# stripPCB002.net
KiCad netlist of a schematic drawn in EAGLE
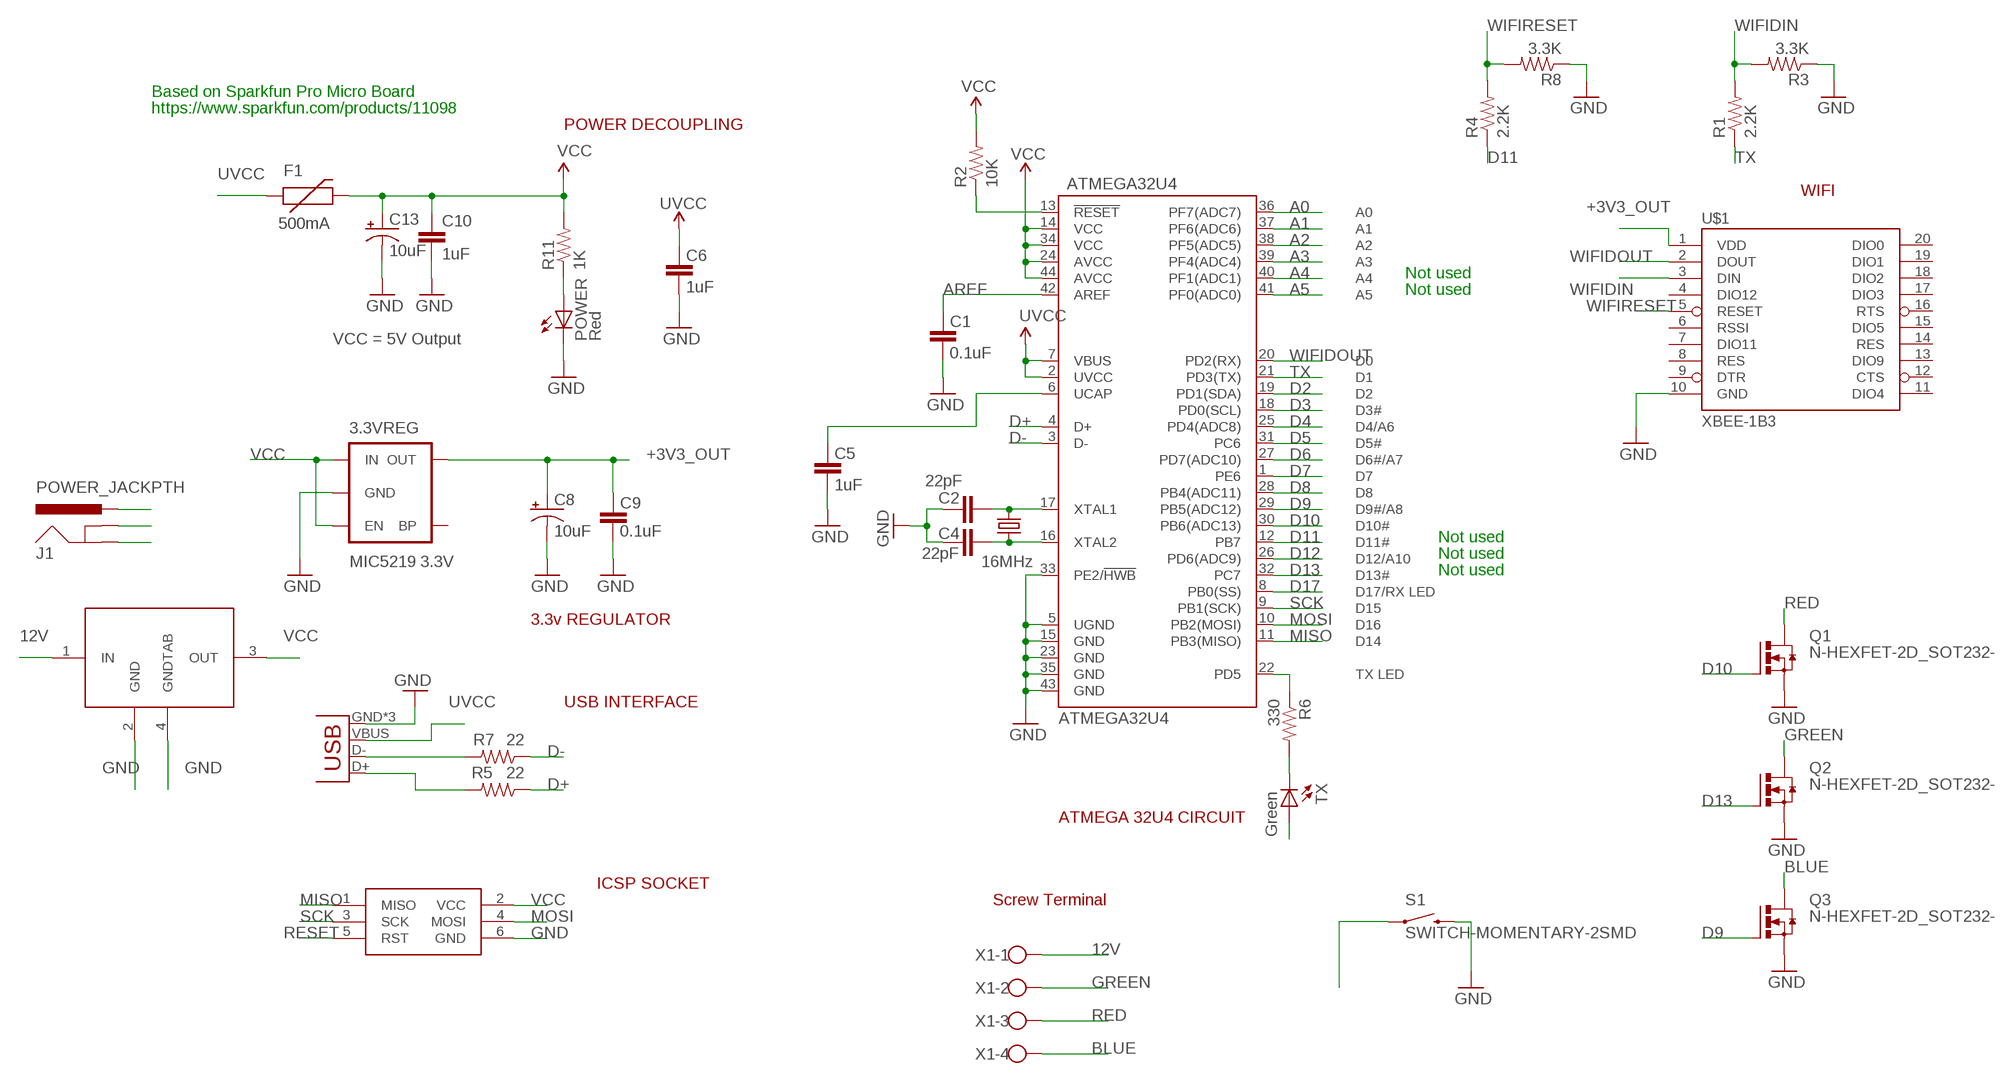
[diagram p0: schematic, sheet 1]

(export (version "E")
  (design (tool "Eeschema 10.0.6"))
  (components
    (comp (ref "3.3VREG")
      (value "MIC5219 3.3V")
      (footprint "eagle-import:SOT23-5")
      (libsource (lib "eagle-import") (part "V_REG_MIC52193.3V"))
    )
    (comp (ref "ATMEGA32U4")
      (value "ATMEGA32U4")
      (footprint "eagle-import:SPARKFUN-DIGITALIC_TQFP44")
      (libsource (lib "eagle-import") (part "ATMEGA32U4TQFP"))
    )
    (comp (ref "C1")
      (value "0.1uF")
      (footprint "eagle-import:0402-CAP")
      (libsource (lib "eagle-import") (part "CAP0402-CAP"))
    )
    (comp (ref "C2")
      (value "22pF")
      (footprint "eagle-import:0402-CAP")
      (libsource (lib "eagle-import") (part "CAP0402-CAP"))
    )
    (comp (ref "C4")
      (value "22pF")
      (footprint "eagle-import:0402-CAP")
      (libsource (lib "eagle-import") (part "CAP0402-CAP"))
    )
    (comp (ref "C5")
      (value "1uF")
      (footprint "eagle-import:0402-CAP")
      (libsource (lib "eagle-import") (part "CAP0402-CAP"))
    )
    (comp (ref "C6")
      (value "1uF")
      (footprint "eagle-import:0402-CAP")
      (libsource (lib "eagle-import") (part "CAP0402-CAP"))
    )
    (comp (ref "C8")
      (value "10uF")
      (footprint "eagle-import:EIA3216")
      (libsource (lib "eagle-import") (part "CAP_POL1206"))
    )
    (comp (ref "C9")
      (value "0.1uF")
      (footprint "eagle-import:0402-CAP")
      (libsource (lib "eagle-import") (part "CAP0402-CAP"))
    )
    (comp (ref "C10")
      (value "1uF")
      (footprint "eagle-import:0402-CAP")
      (libsource (lib "eagle-import") (part "CAP0402-CAP"))
    )
    (comp (ref "C13")
      (value "10uF")
      (footprint "eagle-import:EIA3216")
      (libsource (lib "eagle-import") (part "CAP_POL1206"))
    )
    (comp (ref "F1")
      (value "500mA")
      (footprint "eagle-import:PTC-1206")
      (libsource (lib "eagle-import") (part "PTCSMD"))
    )
    (comp (ref "ISP1")
      (value "AVRISP-6")
      (footprint "eagle-import:AVRISP")
      (libsource (lib "eagle-import") (part "AVRISP-6"))
    )
    (comp (ref "J1")
      (value "POWER_JACKPTH")
      (footprint "eagle-import:POWER_JACK_PTH")
      (libsource (lib "eagle-import") (part "POWER_JACKPTH"))
    )
    (comp (ref "POWER")
      (value "Red")
      (footprint "eagle-import:LED-0603")
      (libsource (lib "eagle-import") (part "LED0603"))
    )
    (comp (ref "Q1")
      (value "N-HEXFET-2D_SOT232-")
      (footprint "eagle-import:SOT223")
      (libsource (lib "eagle-import") (part "N-HEXFET-2D_?-SOT232"))
    )
    (comp (ref "Q2")
      (value "N-HEXFET-2D_SOT232-")
      (footprint "eagle-import:SOT223")
      (libsource (lib "eagle-import") (part "N-HEXFET-2D_?-SOT232"))
    )
    (comp (ref "Q3")
      (value "N-HEXFET-2D_SOT232-")
      (footprint "eagle-import:SOT223")
      (libsource (lib "eagle-import") (part "N-HEXFET-2D_?-SOT232"))
    )
    (comp (ref "R1")
      (value "2.2K")
      (footprint "eagle-import:0402-RES")
      (libsource (lib "eagle-import") (part "RESISTOR0402-RES"))
    )
    (comp (ref "R2")
      (value "10K")
      (footprint "eagle-import:0402-RES")
      (libsource (lib "eagle-import") (part "RESISTOR0402-RES"))
    )
    (comp (ref "R3")
      (value "3.3K")
      (footprint "eagle-import:0402-RES")
      (libsource (lib "eagle-import") (part "RESISTOR0402-RES"))
    )
    (comp (ref "R4")
      (value "2.2K")
      (footprint "eagle-import:0402-RES")
      (libsource (lib "eagle-import") (part "RESISTOR0402-RES"))
    )
    (comp (ref "R5")
      (value "22")
      (footprint "eagle-import:0402-RES")
      (libsource (lib "eagle-import") (part "RESISTOR0402-RES"))
    )
    (comp (ref "R6")
      (value "330")
      (footprint "eagle-import:0402-RES")
      (libsource (lib "eagle-import") (part "RESISTOR0402-RES"))
    )
    (comp (ref "R7")
      (value "22")
      (footprint "eagle-import:0402-RES")
      (libsource (lib "eagle-import") (part "RESISTOR0402-RES"))
    )
    (comp (ref "R8")
      (value "3.3K")
      (footprint "eagle-import:0402-RES")
      (libsource (lib "eagle-import") (part "RESISTOR0402-RES"))
    )
    (comp (ref "R11")
      (value "1K")
      (footprint "eagle-import:0402-RES")
      (libsource (lib "eagle-import") (part "RESISTOR0402-RES"))
    )
    (comp (ref "S1")
      (value "SWITCH-MOMENTARY-2SMD")
      (footprint "eagle-import:TACTILE_SWITCH_SMD")
      (libsource (lib "eagle-import") (part "SWITCH-MOMENTARY-2SMD"))
    )
    (comp (ref "TX")
      (value "Green")
      (footprint "eagle-import:LED-0603")
      (libsource (lib "eagle-import") (part "LED0603"))
    )
    (comp (ref "U$1")
      (value "XBEE-1B3")
      (footprint "eagle-import:XBEE-SMD")
      (libsource (lib "eagle-import") (part "XBEE-1B3"))
    )
    (comp (ref "U$2")
      (value "MIC5239")
      (footprint "eagle-import:SOT223")
      (libsource (lib "eagle-import") (part "MIC5239"))
    )
    (comp (ref "X1")
      (value "W237-4")
      (footprint "eagle-import:W237-4")
      (libsource (lib "eagle-import") (part "W237-4"))
    )
    (comp (ref "X2")
      (value "USB-MICROB")
      (footprint "eagle-import:USB-MICROB")
      (libsource (lib "eagle-import") (part "USB-MICROB"))
    )
    (comp (ref "Y1")
      (value "16MHz")
      (footprint "eagle-import:CRYSTAL-SMD-5X3")
      (libsource (lib "eagle-import") (part "CRYSTAL5X3"))
    )
  )
  (nets
    (net (code "1") (name "/+3V3_OUT") (class "Default")
      (node (ref "3.3VREG") (pin "5") (pinfunction "OUT_5") (pintype "passive"))
      (node (ref "C8") (pin "A") (pinfunction "+_A") (pintype "passive"))
      (node (ref "C9") (pin "2") (pinfunction "2_2") (pintype "passive"))
      (node (ref "U$1") (pin "1") (pinfunction "VDD_1") (pintype "power_in"))
    )
    (net (code "2") (name "/12V") (class "Default")
      (node (ref "J1") (pin "PWR") (pinfunction "PWR_PWR") (pintype "bidirectional"))
      (node (ref "U$2") (pin "1") (pinfunction "IN_1") (pintype "input"))
      (node (ref "X1") (pin "1") (pinfunction "KL_1") (pintype "passive"))
    )
    (net (code "3") (name "/A0") (class "Default")
      (node (ref "ATMEGA32U4") (pin "36") (pinfunction "PF7(ADC7)_36") (pintype "bidirectional"))
    )
    (net (code "4") (name "/A1") (class "Default")
      (node (ref "ATMEGA32U4") (pin "37") (pinfunction "PF6(ADC6)_37") (pintype "bidirectional"))
    )
    (net (code "5") (name "/A2") (class "Default")
      (node (ref "ATMEGA32U4") (pin "38") (pinfunction "PF5(ADC5)_38") (pintype "bidirectional"))
    )
    (net (code "6") (name "/A3") (class "Default")
      (node (ref "ATMEGA32U4") (pin "39") (pinfunction "PF4(ADC4)_39") (pintype "bidirectional"))
    )
    (net (code "7") (name "/A4") (class "Default")
      (node (ref "ATMEGA32U4") (pin "40") (pinfunction "PF1(ADC1)_40") (pintype "bidirectional"))
    )
    (net (code "8") (name "/A5") (class "Default")
      (node (ref "ATMEGA32U4") (pin "41") (pinfunction "PF0(ADC0)_41") (pintype "bidirectional"))
    )
    (net (code "9") (name "/AREF") (class "Default")
      (node (ref "ATMEGA32U4") (pin "42") (pinfunction "AREF_42") (pintype "bidirectional"))
      (node (ref "C1") (pin "2") (pinfunction "2_2") (pintype "passive"))
    )
    (net (code "10") (name "/BLUE") (class "Default")
      (node (ref "Q3") (pin "2") (pinfunction "D_2") (pintype "passive"))
      (node (ref "Q3") (pin "4") (pinfunction "D_4") (pintype "passive"))
      (node (ref "X1") (pin "4") (pinfunction "KL_4") (pintype "passive"))
    )
    (net (code "11") (name "/D+") (class "Default")
      (node (ref "ATMEGA32U4") (pin "4") (pinfunction "D+_4") (pintype "bidirectional"))
      (node (ref "R5") (pin "1") (pinfunction "1_1") (pintype "passive"))
    )
    (net (code "12") (name "/D-") (class "Default")
      (node (ref "ATMEGA32U4") (pin "3") (pinfunction "D-_3") (pintype "bidirectional"))
      (node (ref "R7") (pin "1") (pinfunction "1_1") (pintype "passive"))
    )
    (net (code "13") (name "/D2") (class "Default")
      (node (ref "ATMEGA32U4") (pin "19") (pinfunction "PD1(SDA)_19") (pintype "bidirectional"))
    )
    (net (code "14") (name "/D3") (class "Default")
      (node (ref "ATMEGA32U4") (pin "18") (pinfunction "PD0(SCL)_18") (pintype "bidirectional"))
    )
    (net (code "15") (name "/D4") (class "Default")
      (node (ref "ATMEGA32U4") (pin "25") (pinfunction "PD4(ADC8)_25") (pintype "bidirectional"))
    )
    (net (code "16") (name "/D5") (class "Default")
      (node (ref "ATMEGA32U4") (pin "31") (pinfunction "PC6_31") (pintype "bidirectional"))
    )
    (net (code "17") (name "/D6") (class "Default")
      (node (ref "ATMEGA32U4") (pin "27") (pinfunction "PD7(ADC10)_27") (pintype "bidirectional"))
    )
    (net (code "18") (name "/D7") (class "Default")
      (node (ref "ATMEGA32U4") (pin "1") (pinfunction "PE6_1") (pintype "bidirectional"))
      (node (ref "S1") (pin "1") (pinfunction "1_1") (pintype "passive"))
    )
    (net (code "19") (name "/D8") (class "Default")
      (node (ref "ATMEGA32U4") (pin "28") (pinfunction "PB4(ADC11)_28") (pintype "bidirectional"))
    )
    (net (code "20") (name "/D9") (class "Default")
      (node (ref "ATMEGA32U4") (pin "29") (pinfunction "PB5(ADC12)_29") (pintype "bidirectional"))
      (node (ref "Q3") (pin "1") (pinfunction "G_1") (pintype "passive"))
    )
    (net (code "21") (name "/D10") (class "Default")
      (node (ref "ATMEGA32U4") (pin "30") (pinfunction "PB6(ADC13)_30") (pintype "bidirectional"))
      (node (ref "Q1") (pin "1") (pinfunction "G_1") (pintype "passive"))
    )
    (net (code "22") (name "/D11") (class "Default")
      (node (ref "ATMEGA32U4") (pin "12") (pinfunction "PB7_12") (pintype "bidirectional"))
      (node (ref "R4") (pin "1") (pinfunction "1_1") (pintype "passive"))
    )
    (net (code "23") (name "/D12") (class "Default")
      (node (ref "ATMEGA32U4") (pin "26") (pinfunction "PD6(ADC9)_26") (pintype "bidirectional"))
    )
    (net (code "24") (name "/D13") (class "Default")
      (node (ref "ATMEGA32U4") (pin "32") (pinfunction "PC7_32") (pintype "bidirectional"))
      (node (ref "Q2") (pin "1") (pinfunction "G_1") (pintype "passive"))
    )
    (net (code "25") (name "/D17") (class "Default")
      (node (ref "ATMEGA32U4") (pin "8") (pinfunction "PB0(SS)_8") (pintype "bidirectional"))
    )
    (net (code "26") (name "/GREEN") (class "Default")
      (node (ref "Q2") (pin "2") (pinfunction "D_2") (pintype "passive"))
      (node (ref "Q2") (pin "4") (pinfunction "D_4") (pintype "passive"))
      (node (ref "X1") (pin "2") (pinfunction "KL_2") (pintype "passive"))
    )
    (net (code "27") (name "/MISO") (class "Default")
      (node (ref "ATMEGA32U4") (pin "11") (pinfunction "PB3(MISO)_11") (pintype "bidirectional"))
      (node (ref "ISP1") (pin "1") (pinfunction "MISO_1") (pintype "input"))
    )
    (net (code "28") (name "/MOSI") (class "Default")
      (node (ref "ATMEGA32U4") (pin "10") (pinfunction "PB2(MOSI)_10") (pintype "bidirectional"))
      (node (ref "ISP1") (pin "4") (pinfunction "MOSI_4") (pintype "output"))
    )
    (net (code "29") (name "/RED") (class "Default")
      (node (ref "Q1") (pin "2") (pinfunction "D_2") (pintype "passive"))
      (node (ref "Q1") (pin "4") (pinfunction "D_4") (pintype "passive"))
      (node (ref "X1") (pin "3") (pinfunction "KL_3") (pintype "passive"))
    )
    (net (code "30") (name "/RESET") (class "Default")
      (node (ref "ATMEGA32U4") (pin "13") (pinfunction "~{RESET}_13") (pintype "bidirectional"))
      (node (ref "ISP1") (pin "5") (pinfunction "RST_5") (pintype "output"))
      (node (ref "R2") (pin "1") (pinfunction "1_1") (pintype "passive"))
    )
    (net (code "31") (name "/SCK") (class "Default")
      (node (ref "ATMEGA32U4") (pin "9") (pinfunction "PB1(SCK)_9") (pintype "bidirectional"))
      (node (ref "ISP1") (pin "3") (pinfunction "SCK_3") (pintype "output"))
    )
    (net (code "32") (name "/TX") (class "Default")
      (node (ref "ATMEGA32U4") (pin "21") (pinfunction "PD3(TX)_21") (pintype "bidirectional"))
      (node (ref "R1") (pin "1") (pinfunction "1_1") (pintype "passive"))
    )
    (net (code "33") (name "/WIFIDIN") (class "Default")
      (node (ref "R1") (pin "2") (pinfunction "2_2") (pintype "passive"))
      (node (ref "R3") (pin "2") (pinfunction "2_2") (pintype "passive"))
      (node (ref "U$1") (pin "3") (pinfunction "DIN_3") (pintype "input"))
    )
    (net (code "34") (name "/WIFIDOUT") (class "Default")
      (node (ref "ATMEGA32U4") (pin "20") (pinfunction "PD2(RX)_20") (pintype "bidirectional"))
      (node (ref "U$1") (pin "2") (pinfunction "DOUT_2") (pintype "output"))
    )
    (net (code "35") (name "/WIFIRESET") (class "Default")
      (node (ref "R4") (pin "2") (pinfunction "2_2") (pintype "passive"))
      (node (ref "R8") (pin "2") (pinfunction "2_2") (pintype "passive"))
      (node (ref "U$1") (pin "5") (pinfunction "RESET_5") (pintype "input"))
    )
    (net (code "36") (name "GND") (class "Default")
      (node (ref "3.3VREG") (pin "2") (pinfunction "GND_2") (pintype "input"))
      (node (ref "ATMEGA32U4") (pin "15") (pinfunction "GND_15") (pintype "bidirectional"))
      (node (ref "ATMEGA32U4") (pin "23") (pinfunction "GND_23") (pintype "bidirectional"))
      (node (ref "ATMEGA32U4") (pin "33") (pinfunction "PE2/~{HWB}_33") (pintype "bidirectional"))
      (node (ref "ATMEGA32U4") (pin "35") (pinfunction "GND_35") (pintype "bidirectional"))
      (node (ref "ATMEGA32U4") (pin "43") (pinfunction "GND_43") (pintype "bidirectional"))
      (node (ref "ATMEGA32U4") (pin "5") (pinfunction "UGND_5") (pintype "bidirectional"))
      (node (ref "C1") (pin "1") (pinfunction "1_1") (pintype "passive"))
      (node (ref "C10") (pin "2") (pinfunction "2_2") (pintype "passive"))
      (node (ref "C13") (pin "C") (pinfunction "-_C") (pintype "passive"))
      (node (ref "C2") (pin "2") (pinfunction "2_2") (pintype "passive"))
      (node (ref "C4") (pin "2") (pinfunction "2_2") (pintype "passive"))
      (node (ref "C5") (pin "1") (pinfunction "1_1") (pintype "passive"))
      (node (ref "C6") (pin "1") (pinfunction "1_1") (pintype "passive"))
      (node (ref "C8") (pin "C") (pinfunction "-_C") (pintype "passive"))
      (node (ref "C9") (pin "1") (pinfunction "1_1") (pintype "passive"))
      (node (ref "ISP1") (pin "6") (pinfunction "GND_6") (pintype "power_in"))
      (node (ref "J1") (pin "GND") (pinfunction "GND_GND") (pintype "bidirectional"))
      (node (ref "J1") (pin "GNDBREAK") (pinfunction "GNDBREAK_GNDBREAK") (pintype "bidirectional"))
      (node (ref "POWER") (pin "C") (pinfunction "C_C") (pintype "passive"))
      (node (ref "Q1") (pin "3") (pinfunction "S_3") (pintype "passive"))
      (node (ref "Q2") (pin "3") (pinfunction "S_3") (pintype "passive"))
      (node (ref "Q3") (pin "3") (pinfunction "S_3") (pintype "passive"))
      (node (ref "R3") (pin "1") (pinfunction "1_1") (pintype "passive"))
      (node (ref "R8") (pin "1") (pinfunction "1_1") (pintype "passive"))
      (node (ref "S1") (pin "3") (pinfunction "2_3") (pintype "passive"))
      (node (ref "U$1") (pin "10") (pinfunction "GND_10") (pintype "power_in"))
      (node (ref "U$2") (pin "2") (pinfunction "GND_2") (pintype "power_in"))
      (node (ref "U$2") (pin "4") (pinfunction "GNDTAB_4") (pintype "power_in"))
      (node (ref "X2") (pin "GND") (pinfunction "GND_GND") (pintype "bidirectional"))
      (node (ref "X2") (pin "MT1") (pinfunction "GND_MT1") (pintype "bidirectional"))
      (node (ref "X2") (pin "MT2") (pinfunction "GND_MT2") (pintype "bidirectional"))
    )
    (net (code "37") (name "Net-(ATMEGA32U4-PD5)") (class "Default")
      (node (ref "ATMEGA32U4") (pin "22") (pinfunction "PD5_22") (pintype "bidirectional"))
      (node (ref "R6") (pin "1") (pinfunction "1_1") (pintype "passive"))
    )
    (net (code "38") (name "Net-(ATMEGA32U4-UCAP)") (class "Default")
      (node (ref "ATMEGA32U4") (pin "6") (pinfunction "UCAP_6") (pintype "bidirectional"))
      (node (ref "C5") (pin "2") (pinfunction "2_2") (pintype "passive"))
    )
    (net (code "39") (name "Net-(ATMEGA32U4-XTAL1)") (class "Default")
      (node (ref "ATMEGA32U4") (pin "17") (pinfunction "XTAL1_17") (pintype "bidirectional"))
      (node (ref "C2") (pin "1") (pinfunction "1_1") (pintype "passive"))
      (node (ref "Y1") (pin "3") (pinfunction "2_3") (pintype "passive"))
    )
    (net (code "40") (name "Net-(ATMEGA32U4-XTAL2)") (class "Default")
      (node (ref "ATMEGA32U4") (pin "16") (pinfunction "XTAL2_16") (pintype "bidirectional"))
      (node (ref "C4") (pin "1") (pinfunction "1_1") (pintype "passive"))
      (node (ref "Y1") (pin "1") (pinfunction "1_1") (pintype "passive"))
    )
    (net (code "41") (name "Net-(POWER-PadA)") (class "Default")
      (node (ref "POWER") (pin "A") (pinfunction "A_A") (pintype "passive"))
      (node (ref "R11") (pin "1") (pinfunction "1_1") (pintype "passive"))
    )
    (net (code "42") (name "Net-(R5-Pad2)") (class "Default")
      (node (ref "R5") (pin "2") (pinfunction "2_2") (pintype "passive"))
      (node (ref "X2") (pin "D+") (pinfunction "D+_D+") (pintype "bidirectional"))
    )
    (net (code "43") (name "Net-(R6-Pad2)") (class "Default")
      (node (ref "R6") (pin "2") (pinfunction "2_2") (pintype "passive"))
      (node (ref "TX") (pin "C") (pinfunction "C_C") (pintype "passive"))
    )
    (net (code "44") (name "Net-(R7-Pad2)") (class "Default")
      (node (ref "R7") (pin "2") (pinfunction "2_2") (pintype "passive"))
      (node (ref "X2") (pin "D-") (pinfunction "D-_D-") (pintype "bidirectional"))
    )
    (net (code "45") (name "UVCC") (class "Default")
      (node (ref "ATMEGA32U4") (pin "2") (pinfunction "UVCC_2") (pintype "bidirectional"))
      (node (ref "ATMEGA32U4") (pin "7") (pinfunction "VBUS_7") (pintype "bidirectional"))
      (node (ref "C6") (pin "2") (pinfunction "2_2") (pintype "passive"))
      (node (ref "F1") (pin "1") (pinfunction "1_1") (pintype "bidirectional"))
      (node (ref "X2") (pin "VBUS") (pinfunction "VBUS_VBUS") (pintype "bidirectional"))
    )
    (net (code "46") (name "VCC") (class "Default")
      (node (ref "3.3VREG") (pin "1") (pinfunction "IN_1") (pintype "input"))
      (node (ref "3.3VREG") (pin "3") (pinfunction "EN_3") (pintype "input"))
      (node (ref "ATMEGA32U4") (pin "14") (pinfunction "VCC_14") (pintype "bidirectional"))
      (node (ref "ATMEGA32U4") (pin "24") (pinfunction "AVCC_24") (pintype "bidirectional"))
      (node (ref "ATMEGA32U4") (pin "34") (pinfunction "VCC_34") (pintype "bidirectional"))
      (node (ref "ATMEGA32U4") (pin "44") (pinfunction "AVCC_44") (pintype "bidirectional"))
      (node (ref "C10") (pin "1") (pinfunction "1_1") (pintype "passive"))
      (node (ref "C13") (pin "A") (pinfunction "+_A") (pintype "passive"))
      (node (ref "F1") (pin "2") (pinfunction "2_2") (pintype "bidirectional"))
      (node (ref "ISP1") (pin "2") (pinfunction "VCC_2") (pintype "power_in"))
      (node (ref "R11") (pin "2") (pinfunction "2_2") (pintype "passive"))
      (node (ref "R2") (pin "2") (pinfunction "2_2") (pintype "passive"))
      (node (ref "TX") (pin "A") (pinfunction "A_A") (pintype "passive"))
      (node (ref "U$2") (pin "3") (pinfunction "OUT_3") (pintype "output"))
    )
    (net (code "47") (name "unconnected-(3.3VREG-BP-Pad4)") (class "Default")
      (node (ref "3.3VREG") (pin "4") (pinfunction "BP_4") (pintype "input"))
    )
    (net (code "48") (name "unconnected-(U$1-CTS-Pad12)") (class "Default")
      (node (ref "U$1") (pin "12") (pinfunction "CTS_12") (pintype "output"))
    )
    (net (code "49") (name "unconnected-(U$1-DIO0-Pad20)") (class "Default")
      (node (ref "U$1") (pin "20") (pinfunction "DIO0_20") (pintype "bidirectional"))
    )
    (net (code "50") (name "unconnected-(U$1-DIO1-Pad19)") (class "Default")
      (node (ref "U$1") (pin "19") (pinfunction "DIO1_19") (pintype "bidirectional"))
    )
    (net (code "51") (name "unconnected-(U$1-DIO2-Pad18)") (class "Default")
      (node (ref "U$1") (pin "18") (pinfunction "DIO2_18") (pintype "bidirectional"))
    )
    (net (code "52") (name "unconnected-(U$1-DIO3-Pad17)") (class "Default")
      (node (ref "U$1") (pin "17") (pinfunction "DIO3_17") (pintype "bidirectional"))
    )
    (net (code "53") (name "unconnected-(U$1-DIO4-Pad11)") (class "Default")
      (node (ref "U$1") (pin "11") (pinfunction "DIO4_11") (pintype "bidirectional"))
    )
    (net (code "54") (name "unconnected-(U$1-DIO5-Pad15)") (class "Default")
      (node (ref "U$1") (pin "15") (pinfunction "DIO5_15") (pintype "bidirectional"))
    )
    (net (code "55") (name "unconnected-(U$1-DIO9-Pad13)") (class "Default")
      (node (ref "U$1") (pin "13") (pinfunction "DIO9_13") (pintype "bidirectional"))
    )
    (net (code "56") (name "unconnected-(U$1-DIO11-Pad7)") (class "Default")
      (node (ref "U$1") (pin "7") (pinfunction "DIO11_7") (pintype "bidirectional"))
    )
    (net (code "57") (name "unconnected-(U$1-DIO12-Pad4)") (class "Default")
      (node (ref "U$1") (pin "4") (pinfunction "DIO12_4") (pintype "bidirectional"))
    )
    (net (code "58") (name "unconnected-(U$1-DTR-Pad9)") (class "Default")
      (node (ref "U$1") (pin "9") (pinfunction "DTR_9") (pintype "bidirectional"))
    )
    (net (code "59") (name "unconnected-(U$1-RES-Pad8)") (class "Default")
      (node (ref "U$1") (pin "8") (pinfunction "RES_8") (pintype "bidirectional"))
    )
    (net (code "60") (name "unconnected-(U$1-RES-Pad14)") (class "Default")
      (node (ref "U$1") (pin "14") (pinfunction "RES_14") (pintype "bidirectional"))
    )
    (net (code "61") (name "unconnected-(U$1-RSSI-Pad6)") (class "Default")
      (node (ref "U$1") (pin "6") (pinfunction "RSSI_6") (pintype "bidirectional"))
    )
    (net (code "62") (name "unconnected-(U$1-RTS-Pad16)") (class "Default")
      (node (ref "U$1") (pin "16") (pinfunction "RTS_16") (pintype "input"))
    )
  )
)
